# 4_-RK3399_EDP_CSI_HDMI.net
KiCad netlist of a schematic drawn in Altium Designer
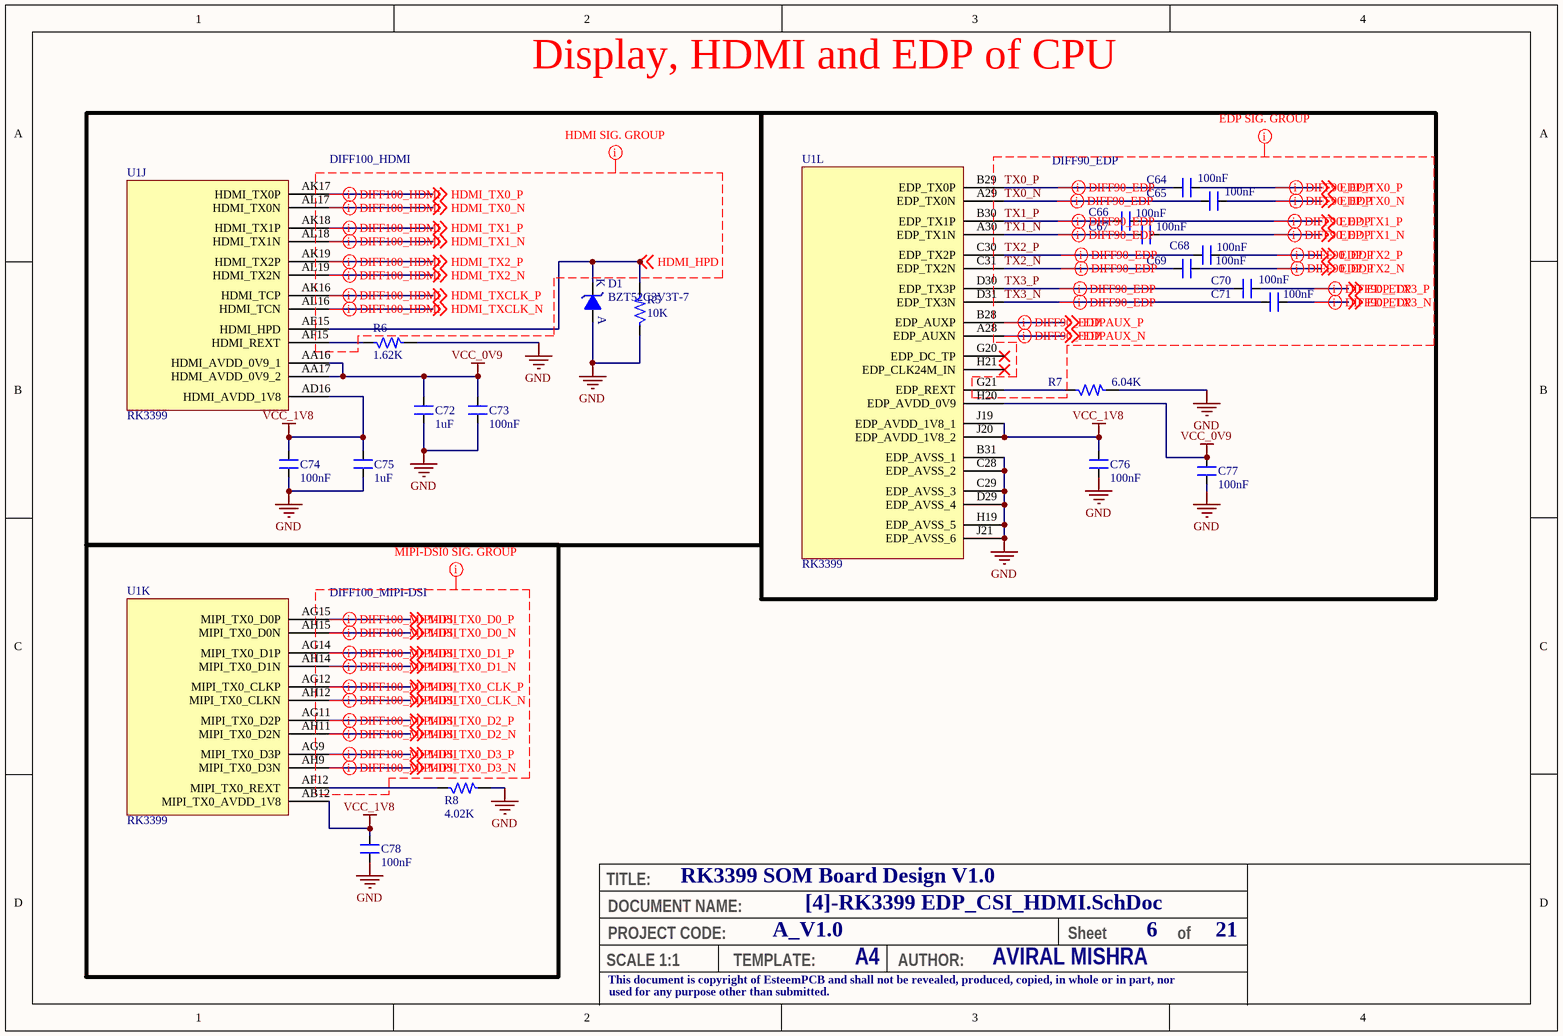
[diagram p0: [4]-RK3399 EDP_CSI_HDMI.SchDoc]

(export (version "E")
  (design (tool "Eeschema 10.0.6"))
  (components
    (comp (ref "C64")
      (value "100nF")
      (footprint "CAP_0201")
      (description "0.1µF ±10% 25V Ceramic Capacitor X5R 0201 (0603 Metric)")
      (fields
        (field (name "MANUFACTURER") "TDK Corporation")
        (field (name "MANUFACTURER PART NUMBER") "C0603X5R1E104K030BB")
      )
      (libsource (lib "RK3399 _Module_Intlib") (part "CAP_100nF-25V-10%-0201"))
    )
    (comp (ref "C65")
      (value "100nF")
      (footprint "CAP_0201")
      (description "0.1µF ±10% 25V Ceramic Capacitor X5R 0201 (0603 Metric)")
      (fields
        (field (name "MANUFACTURER") "TDK Corporation")
        (field (name "MANUFACTURER PART NUMBER") "C0603X5R1E104K030BB")
      )
      (libsource (lib "RK3399 _Module_Intlib") (part "CAP_100nF-25V-10%-0201"))
    )
    (comp (ref "C66")
      (value "100nF")
      (footprint "CAP_0201")
      (description "0.1µF ±10% 25V Ceramic Capacitor X5R 0201 (0603 Metric)")
      (fields
        (field (name "MANUFACTURER") "TDK Corporation")
        (field (name "MANUFACTURER PART NUMBER") "C0603X5R1E104K030BB")
      )
      (libsource (lib "RK3399 _Module_Intlib") (part "CAP_100nF-25V-10%-0201"))
    )
    (comp (ref "C67")
      (value "100nF")
      (footprint "CAP_0201")
      (description "0.1µF ±10% 25V Ceramic Capacitor X5R 0201 (0603 Metric)")
      (fields
        (field (name "MANUFACTURER") "TDK Corporation")
        (field (name "MANUFACTURER PART NUMBER") "C0603X5R1E104K030BB")
      )
      (libsource (lib "RK3399 _Module_Intlib") (part "CAP_100nF-25V-10%-0201"))
    )
    (comp (ref "C68")
      (value "100nF")
      (footprint "CAP_0201")
      (description "0.1µF ±10% 25V Ceramic Capacitor X5R 0201 (0603 Metric)")
      (fields
        (field (name "MANUFACTURER") "TDK Corporation")
        (field (name "MANUFACTURER PART NUMBER") "C0603X5R1E104K030BB")
      )
      (libsource (lib "RK3399 _Module_Intlib") (part "CAP_100nF-25V-10%-0201"))
    )
    (comp (ref "C69")
      (value "100nF")
      (footprint "CAP_0201")
      (description "0.1µF ±10% 25V Ceramic Capacitor X5R 0201 (0603 Metric)")
      (fields
        (field (name "MANUFACTURER") "TDK Corporation")
        (field (name "MANUFACTURER PART NUMBER") "C0603X5R1E104K030BB")
      )
      (libsource (lib "RK3399 _Module_Intlib") (part "CAP_100nF-25V-10%-0201"))
    )
    (comp (ref "C70")
      (value "100nF")
      (footprint "CAP_0201")
      (description "0.1µF ±10% 25V Ceramic Capacitor X5R 0201 (0603 Metric)")
      (fields
        (field (name "MANUFACTURER") "TDK Corporation")
        (field (name "MANUFACTURER PART NUMBER") "C0603X5R1E104K030BB")
      )
      (libsource (lib "RK3399 _Module_Intlib") (part "CAP_100nF-25V-10%-0201"))
    )
    (comp (ref "C71")
      (value "100nF")
      (footprint "CAP_0201")
      (description "0.1µF ±10% 25V Ceramic Capacitor X5R 0201 (0603 Metric)")
      (fields
        (field (name "MANUFACTURER") "TDK Corporation")
        (field (name "MANUFACTURER PART NUMBER") "C0603X5R1E104K030BB")
      )
      (libsource (lib "RK3399 _Module_Intlib") (part "CAP_100nF-25V-10%-0201"))
    )
    (comp (ref "C72")
      (value "1uF")
      (footprint "CAP_0201")
      (description "1µF ±20% 16V Ceramic Capacitor X5R 0201 (0603 Metric)")
      (fields
        (field (name "MANUFACTURER") "Samsung Electro-Mechanics")
        (field (name "MANUFACTURER PART NUMBER") "CL03A105MO3NRNH")
      )
      (libsource (lib "RK3399 _Module_Intlib") (part "CAP_1uF-16V-10%-0201"))
    )
    (comp (ref "C73")
      (value "100nF")
      (footprint "CAP_0201")
      (description "0.1µF ±10% 25V Ceramic Capacitor X5R 0201 (0603 Metric)")
      (fields
        (field (name "MANUFACTURER") "TDK Corporation")
        (field (name "MANUFACTURER PART NUMBER") "C0603X5R1E104K030BB")
      )
      (libsource (lib "RK3399 _Module_Intlib") (part "CAP_100nF-25V-10%-0201"))
    )
    (comp (ref "C74")
      (value "100nF")
      (footprint "CAP_0201")
      (description "0.1µF ±10% 25V Ceramic Capacitor X5R 0201 (0603 Metric)")
      (fields
        (field (name "MANUFACTURER") "TDK Corporation")
        (field (name "MANUFACTURER PART NUMBER") "C0603X5R1E104K030BB")
      )
      (libsource (lib "RK3399 _Module_Intlib") (part "CAP_100nF-25V-10%-0201"))
    )
    (comp (ref "C75")
      (value "1uF")
      (footprint "CAP_0201")
      (description "1µF ±20% 16V Ceramic Capacitor X5R 0201 (0603 Metric)")
      (fields
        (field (name "MANUFACTURER") "Samsung Electro-Mechanics")
        (field (name "MANUFACTURER PART NUMBER") "CL03A105MO3NRNH")
      )
      (libsource (lib "RK3399 _Module_Intlib") (part "CAP_1uF-16V-10%-0201"))
    )
    (comp (ref "C76")
      (value "100nF")
      (footprint "CAP_0201")
      (description "0.1µF ±10% 25V Ceramic Capacitor X5R 0201 (0603 Metric)")
      (fields
        (field (name "MANUFACTURER") "TDK Corporation")
        (field (name "MANUFACTURER PART NUMBER") "C0603X5R1E104K030BB")
      )
      (libsource (lib "RK3399 _Module_Intlib") (part "CAP_100nF-25V-10%-0201"))
    )
    (comp (ref "C77")
      (value "100nF")
      (footprint "CAP_0201")
      (description "0.1µF ±10% 25V Ceramic Capacitor X5R 0201 (0603 Metric)")
      (fields
        (field (name "MANUFACTURER") "TDK Corporation")
        (field (name "MANUFACTURER PART NUMBER") "C0603X5R1E104K030BB")
      )
      (libsource (lib "RK3399 _Module_Intlib") (part "CAP_100nF-25V-10%-0201"))
    )
    (comp (ref "C78")
      (value "100nF")
      (footprint "CAP_0201")
      (description "0.1µF ±10% 25V Ceramic Capacitor X5R 0201 (0603 Metric)")
      (fields
        (field (name "MANUFACTURER") "TDK Corporation")
        (field (name "MANUFACTURER PART NUMBER") "C0603X5R1E104K030BB")
      )
      (libsource (lib "RK3399 _Module_Intlib") (part "CAP_100nF-25V-10%-0201"))
    )
    (comp (ref "D1")
      (value "BZT52C3V3T-7")
      (footprint "DIO_SOD523")
      (description "Zener Diode 3.3V 300mW ±6% Surface Mount SOD-523")
      (fields (field (name "MANUFACTURER") "Diodes Incorporated"))
      (libsource (lib "RK3399 _Module_Schlib") (part "DIO-Z_3.3V-300mW-SOD-523"))
    )
    (comp (ref "R5")
      (value "10K")
      (footprint "RES_0201")
      (description "10 kOhms ±1% 0.05W, 1/20W Chip Resistor 0201 (0603 Metric) Thick Film")
      (fields
        (field (name "MANUFACTURER") "Stackpole Electronics Inc")
        (field (name "MANUFACTURER PART NUMBER") "RMCF0201FT10K0")
      )
      (libsource (lib "RK3399 _Module_Intlib") (part "RES_10K-0.05W-1%-0201"))
    )
    (comp (ref "R6")
      (value "1.62K")
      (footprint "RES_0201")
      (description "1.62 kOhms ±1% 0.05W, 1/20W Chip Resistor 0201 (0603 Metric) Automotive AEC-Q200 Thick Film")
      (fields
        (field (name "MANUFACTURER") "Panasonic Electronic Components")
        (field (name "MANUFACTURER PART NUMBER") "ERJ-1GNF1621C")
      )
      (libsource (lib "RK3399 _Module_Intlib") (part "RES_1.62K-0.05W-1%-0201"))
    )
    (comp (ref "R7")
      (value "6.04K")
      (footprint "RES_0201")
      (description "6.04 kOhms ±1% 0.05W, 1/20W Chip Resistor 0201 (0603 Metric) Thick Film")
      (fields
        (field (name "MANUFACTURER") "Panasonic Electronic Components")
        (field (name "MANUFACTURER PART NUMBER") "ERJ-1GEF6041C")
      )
      (libsource (lib "RK3399 _Module_Intlib") (part "RES_6.04K-0.05W-1%-0201"))
    )
    (comp (ref "R8")
      (value "4.02K")
      (footprint "RES_0201")
      (description "4.02 kOhms ±1% 0.05W, 1/20W Chip Resistor 0201 (0603 Metric) Thick Film")
      (fields
        (field (name "MANUFACTURER") "Yageo")
        (field (name "MANUFACTURER PART NUMBER") "RC0201FR-074K02L")
      )
      (libsource (lib "RK3399 _Module_Intlib") (part "RES_4.02K-0.05W-1%-0201"))
    )
    (comp (ref "U1")
      (value "RK3399")
      (footprint "FBGA828_23_826X826")
      (description "RK3399 is a low power, high performance processor for computing, personal mobile.")
      (fields (field (name "MANUFACTURER") "Rockchip"))
      (libsource (lib "RK3399 _Module_Schlib") (part "IC_RK3399-FCBGA828"))
    )
  )
  (nets
    (net (code "1") (name "/TX0_N") (class "Default")
      (node (ref "C65") (pin "2") (pinfunction "2_2") (pintype "passive"))
      (node (ref "U1") (pin "A29") (pinfunction "EDP_TX0N_A29") (pintype "passive"))
    )
    (net (code "2") (name "/TX0_P") (class "Default")
      (node (ref "C64") (pin "2") (pinfunction "2_2") (pintype "passive"))
      (node (ref "U1") (pin "B29") (pinfunction "EDP_TX0P_B29") (pintype "passive"))
    )
    (net (code "3") (name "/TX1_N") (class "Default")
      (node (ref "C67") (pin "2") (pinfunction "2_2") (pintype "passive"))
      (node (ref "U1") (pin "A30") (pinfunction "EDP_TX1N_A30") (pintype "passive"))
    )
    (net (code "4") (name "/TX1_P") (class "Default")
      (node (ref "C66") (pin "2") (pinfunction "2_2") (pintype "passive"))
      (node (ref "U1") (pin "B30") (pinfunction "EDP_TX1P_B30") (pintype "passive"))
    )
    (net (code "5") (name "/TX2_N") (class "Default")
      (node (ref "C69") (pin "2") (pinfunction "2_2") (pintype "passive"))
      (node (ref "U1") (pin "C31") (pinfunction "EDP_TX2N_C31") (pintype "passive"))
    )
    (net (code "6") (name "/TX2_P") (class "Default")
      (node (ref "C68") (pin "2") (pinfunction "2_2") (pintype "passive"))
      (node (ref "U1") (pin "C30") (pinfunction "EDP_TX2P_C30") (pintype "passive"))
    )
    (net (code "7") (name "/TX3_N") (class "Default")
      (node (ref "C71") (pin "2") (pinfunction "2_2") (pintype "passive"))
      (node (ref "U1") (pin "D31") (pinfunction "EDP_TX3N_D31") (pintype "passive"))
    )
    (net (code "8") (name "/TX3_P") (class "Default")
      (node (ref "C70") (pin "2") (pinfunction "2_2") (pintype "passive"))
      (node (ref "U1") (pin "D30") (pinfunction "EDP_TX3P_D30") (pintype "passive"))
    )
    (net (code "9") (name "EDPAUX_N") (class "Default")
      (node (ref "U1") (pin "A28") (pinfunction "EDP_AUXN_A28") (pintype "passive"))
    )
    (net (code "10") (name "EDPAUX_P") (class "Default")
      (node (ref "U1") (pin "B28") (pinfunction "EDP_AUXP_B28") (pintype "passive"))
    )
    (net (code "11") (name "EDP_TX0_N") (class "Default")
      (node (ref "C65") (pin "1") (pinfunction "1_1") (pintype "passive"))
    )
    (net (code "12") (name "EDP_TX0_P") (class "Default")
      (node (ref "C64") (pin "1") (pinfunction "1_1") (pintype "passive"))
    )
    (net (code "13") (name "EDP_TX1_N") (class "Default")
      (node (ref "C67") (pin "1") (pinfunction "1_1") (pintype "passive"))
    )
    (net (code "14") (name "EDP_TX1_P") (class "Default")
      (node (ref "C66") (pin "1") (pinfunction "1_1") (pintype "passive"))
    )
    (net (code "15") (name "EDP_TX2_N") (class "Default")
      (node (ref "C69") (pin "1") (pinfunction "1_1") (pintype "passive"))
    )
    (net (code "16") (name "EDP_TX2_P") (class "Default")
      (node (ref "C68") (pin "1") (pinfunction "1_1") (pintype "passive"))
    )
    (net (code "17") (name "EDP_TX3_N") (class "Default")
      (node (ref "C71") (pin "1") (pinfunction "1_1") (pintype "passive"))
    )
    (net (code "18") (name "EDP_TX3_P") (class "Default")
      (node (ref "C70") (pin "1") (pinfunction "1_1") (pintype "passive"))
    )
    (net (code "19") (name "GND") (class "Default")
      (node (ref "C72") (pin "1") (pinfunction "1_1") (pintype "passive"))
      (node (ref "C73") (pin "1") (pinfunction "1_1") (pintype "passive"))
      (node (ref "C74") (pin "1") (pinfunction "1_1") (pintype "passive"))
      (node (ref "C75") (pin "1") (pinfunction "1_1") (pintype "passive"))
      (node (ref "C76") (pin "2") (pinfunction "2_2") (pintype "passive"))
      (node (ref "C77") (pin "1") (pinfunction "1_1") (pintype "passive"))
      (node (ref "C78") (pin "1") (pinfunction "1_1") (pintype "passive"))
      (node (ref "D1") (pin "A") (pinfunction "A_A") (pintype "passive"))
      (node (ref "R5") (pin "1") (pinfunction "1_1") (pintype "passive"))
      (node (ref "R6") (pin "2") (pinfunction "2_2") (pintype "passive"))
      (node (ref "R7") (pin "2") (pinfunction "2_2") (pintype "passive"))
      (node (ref "R8") (pin "2") (pinfunction "2_2") (pintype "passive"))
      (node (ref "U1") (pin "B31") (pinfunction "EDP_AVSS_1_B31") (pintype "passive"))
      (node (ref "U1") (pin "C28") (pinfunction "EDP_AVSS_2_C28") (pintype "passive"))
      (node (ref "U1") (pin "C29") (pinfunction "EDP_AVSS_3_C29") (pintype "passive"))
      (node (ref "U1") (pin "D29") (pinfunction "EDP_AVSS_4_D29") (pintype "passive"))
      (node (ref "U1") (pin "H19") (pinfunction "EDP_AVSS_5_H19") (pintype "passive"))
      (node (ref "U1") (pin "J21") (pinfunction "EDP_AVSS_6_J21") (pintype "passive"))
    )
    (net (code "20") (name "HDMI_HPD") (class "Default")
      (node (ref "D1") (pin "K") (pinfunction "K_K") (pintype "passive"))
      (node (ref "R5") (pin "2") (pinfunction "2_2") (pintype "passive"))
      (node (ref "U1") (pin "AE15") (pinfunction "HDMI_HPD_AE15") (pintype "passive"))
    )
    (net (code "21") (name "HDMI_TX0_N") (class "Default")
      (node (ref "U1") (pin "AL17") (pinfunction "HDMI_TX0N_AL17") (pintype "passive"))
    )
    (net (code "22") (name "HDMI_TX0_P") (class "Default")
      (node (ref "U1") (pin "AK17") (pinfunction "HDMI_TX0P_AK17") (pintype "passive"))
    )
    (net (code "23") (name "HDMI_TX1_N") (class "Default")
      (node (ref "U1") (pin "AL18") (pinfunction "HDMI_TX1N_AL18") (pintype "passive"))
    )
    (net (code "24") (name "HDMI_TX1_P") (class "Default")
      (node (ref "U1") (pin "AK18") (pinfunction "HDMI_TX1P_AK18") (pintype "passive"))
    )
    (net (code "25") (name "HDMI_TX2_N") (class "Default")
      (node (ref "U1") (pin "AL19") (pinfunction "HDMI_TX2N_AL19") (pintype "passive"))
    )
    (net (code "26") (name "HDMI_TX2_P") (class "Default")
      (node (ref "U1") (pin "AK19") (pinfunction "HDMI_TX2P_AK19") (pintype "passive"))
    )
    (net (code "27") (name "HDMI_TXCLK_N") (class "Default")
      (node (ref "U1") (pin "AL16") (pinfunction "HDMI_TCN_AL16") (pintype "passive"))
    )
    (net (code "28") (name "HDMI_TXCLK_P") (class "Default")
      (node (ref "U1") (pin "AK16") (pinfunction "HDMI_TCP_AK16") (pintype "passive"))
    )
    (net (code "29") (name "MIPI_TX0_CLK_N") (class "Default")
      (node (ref "U1") (pin "AH12") (pinfunction "MIPI_TX0_CLKN_AH12") (pintype "passive"))
    )
    (net (code "30") (name "MIPI_TX0_CLK_P") (class "Default")
      (node (ref "U1") (pin "AG12") (pinfunction "MIPI_TX0_CLKP_AG12") (pintype "passive"))
    )
    (net (code "31") (name "MIPI_TX0_D0_N") (class "Default")
      (node (ref "U1") (pin "AH15") (pinfunction "MIPI_TX0_D0N_AH15") (pintype "passive"))
    )
    (net (code "32") (name "MIPI_TX0_D0_P") (class "Default")
      (node (ref "U1") (pin "AG15") (pinfunction "MIPI_TX0_D0P_AG15") (pintype "passive"))
    )
    (net (code "33") (name "MIPI_TX0_D1_N") (class "Default")
      (node (ref "U1") (pin "AH14") (pinfunction "MIPI_TX0_D1N_AH14") (pintype "passive"))
    )
    (net (code "34") (name "MIPI_TX0_D1_P") (class "Default")
      (node (ref "U1") (pin "AG14") (pinfunction "MIPI_TX0_D1P_AG14") (pintype "passive"))
    )
    (net (code "35") (name "MIPI_TX0_D2_N") (class "Default")
      (node (ref "U1") (pin "AH11") (pinfunction "MIPI_TX0_D2N_AH11") (pintype "passive"))
    )
    (net (code "36") (name "MIPI_TX0_D2_P") (class "Default")
      (node (ref "U1") (pin "AG11") (pinfunction "MIPI_TX0_D2P_AG11") (pintype "passive"))
    )
    (net (code "37") (name "MIPI_TX0_D3_N") (class "Default")
      (node (ref "U1") (pin "AH9") (pinfunction "MIPI_TX0_D3N_AH9") (pintype "passive"))
    )
    (net (code "38") (name "MIPI_TX0_D3_P") (class "Default")
      (node (ref "U1") (pin "AG9") (pinfunction "MIPI_TX0_D3P_AG9") (pintype "passive"))
    )
    (net (code "39") (name "Net-(U1J-HDMI_REXT)") (class "Default")
      (node (ref "R6") (pin "1") (pinfunction "1_1") (pintype "passive"))
      (node (ref "U1") (pin "AF15") (pinfunction "HDMI_REXT_AF15") (pintype "passive"))
    )
    (net (code "40") (name "Net-(U1K-MIPI_TX0_REXT)") (class "Default")
      (node (ref "R8") (pin "1") (pinfunction "1_1") (pintype "passive"))
      (node (ref "U1") (pin "AF12") (pinfunction "MIPI_TX0_REXT_AF12") (pintype "passive"))
    )
    (net (code "41") (name "Net-(U1L-EDP_REXT)") (class "Default")
      (node (ref "R7") (pin "1") (pinfunction "1_1") (pintype "passive"))
      (node (ref "U1") (pin "G21") (pinfunction "EDP_REXT_G21") (pintype "passive"))
    )
    (net (code "42") (name "VCC_0V9") (class "Default")
      (node (ref "C72") (pin "2") (pinfunction "2_2") (pintype "passive"))
      (node (ref "C73") (pin "2") (pinfunction "2_2") (pintype "passive"))
      (node (ref "C77") (pin "2") (pinfunction "2_2") (pintype "passive"))
      (node (ref "U1") (pin "AA16") (pinfunction "HDMI_AVDD_0V9_1_AA16") (pintype "passive"))
      (node (ref "U1") (pin "AA17") (pinfunction "HDMI_AVDD_0V9_2_AA17") (pintype "passive"))
      (node (ref "U1") (pin "H20") (pinfunction "EDP_AVDD_0V9_H20") (pintype "passive"))
    )
    (net (code "43") (name "VCC_1V8") (class "Default")
      (node (ref "C74") (pin "2") (pinfunction "2_2") (pintype "passive"))
      (node (ref "C75") (pin "2") (pinfunction "2_2") (pintype "passive"))
      (node (ref "C76") (pin "1") (pinfunction "1_1") (pintype "passive"))
      (node (ref "C78") (pin "2") (pinfunction "2_2") (pintype "passive"))
      (node (ref "U1") (pin "AB12") (pinfunction "MIPI_TX0_AVDD_1V8_AB12") (pintype "passive"))
      (node (ref "U1") (pin "AD16") (pinfunction "HDMI_AVDD_1V8_AD16") (pintype "passive"))
      (node (ref "U1") (pin "J19") (pinfunction "EDP_AVDD_1V8_1_J19") (pintype "passive"))
      (node (ref "U1") (pin "J20") (pinfunction "EDP_AVDD_1V8_2_J20") (pintype "passive"))
    )
    (net (code "44") (name "unconnected-(U1L-EDP_CLK24M_IN-PadH21)") (class "Default")
      (node (ref "U1") (pin "H21") (pinfunction "EDP_CLK24M_IN_H21") (pintype "passive+no_connect"))
    )
    (net (code "45") (name "unconnected-(U1L-EDP_DC_TP-PadG20)") (class "Default")
      (node (ref "U1") (pin "G20") (pinfunction "EDP_DC_TP_G20") (pintype "passive+no_connect"))
    )
  )
)
